# featherwing_RGBLEDmatrixPanel.net
KiCad netlist of a schematic drawn in EAGLE
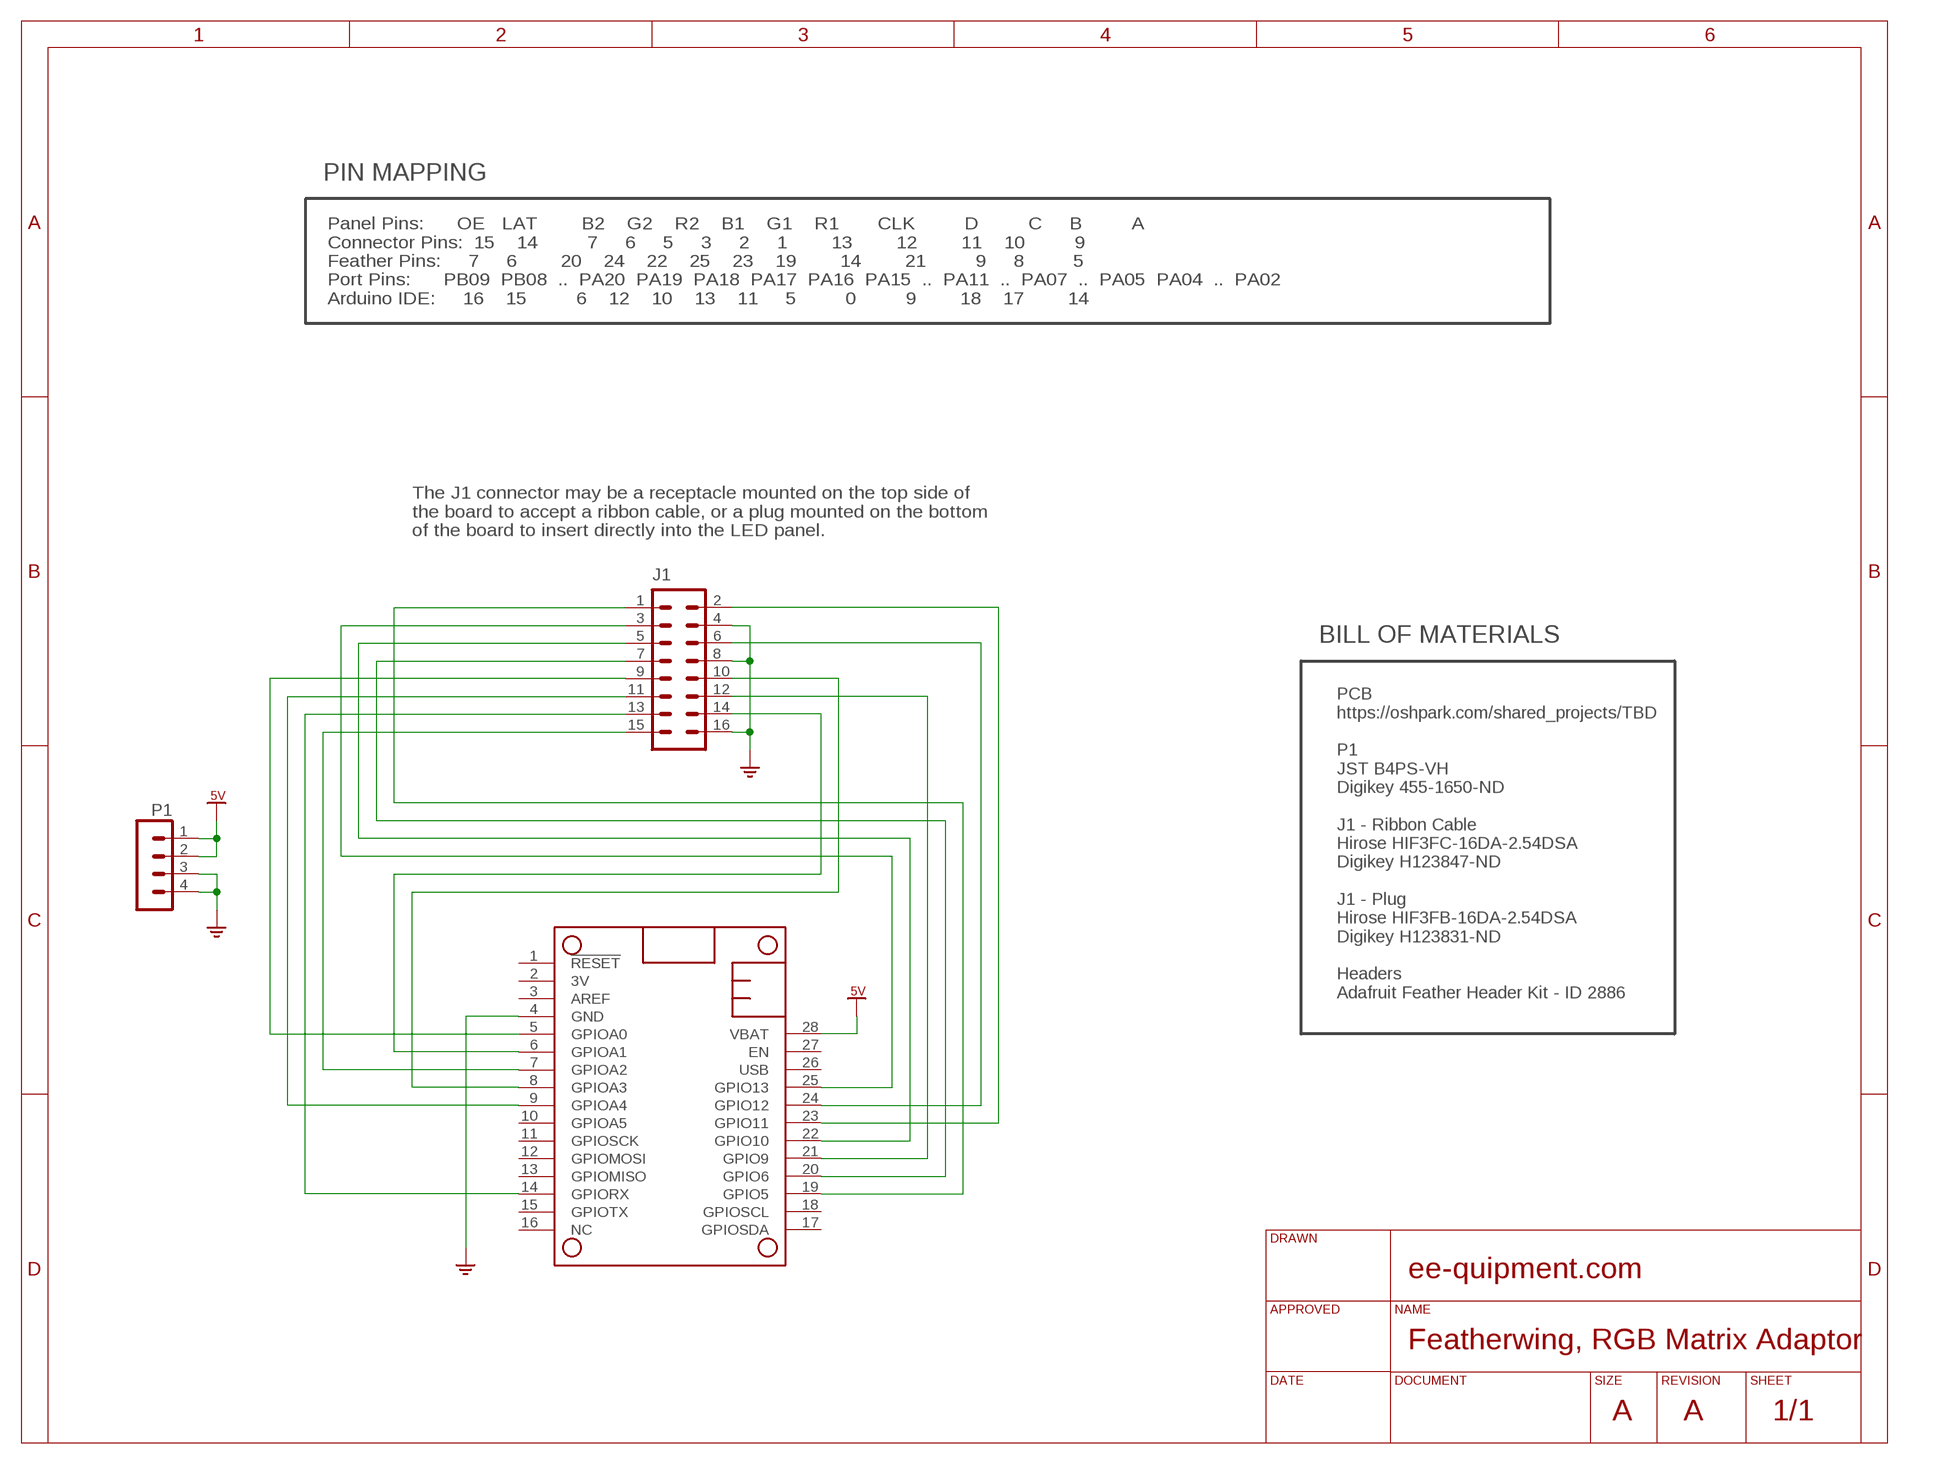
[diagram p0: schematic, sheet 1]

(export (version "E")
  (design (tool "Eeschema 10.0.6"))
  (components
    (comp (ref "J1")
      (value "HDR_16")
      (footprint "eagle-import:HDR_16")
      (libsource (lib "eagle-import") (part "HDR_16"))
    )
    (comp (ref "MS1")
      (value "MICROSHIELD")
      (footprint "eagle-import:MICROSHIELD")
      (libsource (lib "eagle-import") (part "MICROSHIELD"))
    )
    (comp (ref "P1")
      (value "JST_B4P-VHRA")
      (footprint "eagle-import:JST_B4PS-VH")
      (libsource (lib "eagle-import") (part "JST_B4P-VHRA"))
    )
  )
  (nets
    (net (code "1") (name "/3V") (class "Default")
      (node (ref "MS1") (pin "2") (pinfunction "3V_2") (pintype "power_in"))
    )
    (net (code "2") (name "/USB") (class "Default")
      (node (ref "MS1") (pin "26") (pinfunction "USB_26") (pintype "power_in"))
    )
    (net (code "3") (name "5V") (class "Default")
      (node (ref "MS1") (pin "28") (pinfunction "VBAT_28") (pintype "power_in"))
      (node (ref "P1") (pin "1") (pinfunction "1_1") (pintype "passive"))
      (node (ref "P1") (pin "2") (pinfunction "2_2") (pintype "passive"))
    )
    (net (code "4") (name "GND") (class "Default")
      (node (ref "J1") (pin "16") (pinfunction "16_16") (pintype "passive"))
      (node (ref "J1") (pin "4") (pinfunction "4_4") (pintype "passive"))
      (node (ref "J1") (pin "8") (pinfunction "8_8") (pintype "passive"))
      (node (ref "MS1") (pin "4") (pinfunction "GND_4") (pintype "power_in"))
      (node (ref "P1") (pin "3") (pinfunction "3_3") (pintype "passive"))
      (node (ref "P1") (pin "4") (pinfunction "4_4") (pintype "passive"))
    )
    (net (code "5") (name "Net-(MS1-GPIO5)") (class "Default")
      (node (ref "J1") (pin "1") (pinfunction "1_1") (pintype "passive"))
      (node (ref "MS1") (pin "19") (pinfunction "GPIO5_19") (pintype "bidirectional"))
    )
    (net (code "6") (name "Net-(MS1-GPIO6)") (class "Default")
      (node (ref "J1") (pin "7") (pinfunction "7_7") (pintype "passive"))
      (node (ref "MS1") (pin "20") (pinfunction "GPIO6_20") (pintype "bidirectional"))
    )
    (net (code "7") (name "Net-(MS1-GPIO9)") (class "Default")
      (node (ref "J1") (pin "12") (pinfunction "12_12") (pintype "passive"))
      (node (ref "MS1") (pin "21") (pinfunction "GPIO9_21") (pintype "bidirectional"))
    )
    (net (code "8") (name "Net-(MS1-GPIO10)") (class "Default")
      (node (ref "J1") (pin "5") (pinfunction "5_5") (pintype "passive"))
      (node (ref "MS1") (pin "22") (pinfunction "GPIO10_22") (pintype "bidirectional"))
    )
    (net (code "9") (name "Net-(MS1-GPIO11)") (class "Default")
      (node (ref "J1") (pin "2") (pinfunction "2_2") (pintype "passive"))
      (node (ref "MS1") (pin "23") (pinfunction "GPIO11_23") (pintype "bidirectional"))
    )
    (net (code "10") (name "Net-(MS1-GPIO12)") (class "Default")
      (node (ref "J1") (pin "6") (pinfunction "6_6") (pintype "passive"))
      (node (ref "MS1") (pin "24") (pinfunction "GPIO12_24") (pintype "bidirectional"))
    )
    (net (code "11") (name "Net-(MS1-GPIO13)") (class "Default")
      (node (ref "J1") (pin "3") (pinfunction "3_3") (pintype "passive"))
      (node (ref "MS1") (pin "25") (pinfunction "GPIO13_25") (pintype "bidirectional"))
    )
    (net (code "12") (name "Net-(MS1-GPIOA0)") (class "Default")
      (node (ref "J1") (pin "9") (pinfunction "9_9") (pintype "passive"))
      (node (ref "MS1") (pin "5") (pinfunction "GPIOA0_5") (pintype "bidirectional"))
    )
    (net (code "13") (name "Net-(MS1-GPIOA1)") (class "Default")
      (node (ref "J1") (pin "14") (pinfunction "14_14") (pintype "passive"))
      (node (ref "MS1") (pin "6") (pinfunction "GPIOA1_6") (pintype "bidirectional"))
    )
    (net (code "14") (name "Net-(MS1-GPIOA2)") (class "Default")
      (node (ref "J1") (pin "15") (pinfunction "15_15") (pintype "passive"))
      (node (ref "MS1") (pin "7") (pinfunction "GPIOA2_7") (pintype "bidirectional"))
    )
    (net (code "15") (name "Net-(MS1-GPIOA3)") (class "Default")
      (node (ref "J1") (pin "10") (pinfunction "10_10") (pintype "passive"))
      (node (ref "MS1") (pin "8") (pinfunction "GPIOA3_8") (pintype "bidirectional"))
    )
    (net (code "16") (name "Net-(MS1-GPIOA4)") (class "Default")
      (node (ref "J1") (pin "11") (pinfunction "11_11") (pintype "passive"))
      (node (ref "MS1") (pin "9") (pinfunction "GPIOA4_9") (pintype "bidirectional"))
    )
    (net (code "17") (name "Net-(MS1-GPIORX)") (class "Default")
      (node (ref "J1") (pin "13") (pinfunction "13_13") (pintype "passive"))
      (node (ref "MS1") (pin "14") (pinfunction "GPIORX_14") (pintype "bidirectional"))
    )
    (net (code "18") (name "unconnected-(MS1-AREF-Pad3)") (class "Default")
      (node (ref "MS1") (pin "3") (pinfunction "AREF_3") (pintype "passive"))
    )
    (net (code "19") (name "unconnected-(MS1-EN-Pad27)") (class "Default")
      (node (ref "MS1") (pin "27") (pinfunction "EN_27") (pintype "passive"))
    )
    (net (code "20") (name "unconnected-(MS1-GPIOA5-Pad10)") (class "Default")
      (node (ref "MS1") (pin "10") (pinfunction "GPIOA5_10") (pintype "bidirectional"))
    )
    (net (code "21") (name "unconnected-(MS1-GPIOMISO-Pad13)") (class "Default")
      (node (ref "MS1") (pin "13") (pinfunction "GPIOMISO_13") (pintype "bidirectional"))
    )
    (net (code "22") (name "unconnected-(MS1-GPIOMOSI-Pad12)") (class "Default")
      (node (ref "MS1") (pin "12") (pinfunction "GPIOMOSI_12") (pintype "bidirectional"))
    )
    (net (code "23") (name "unconnected-(MS1-GPIOSCK-Pad11)") (class "Default")
      (node (ref "MS1") (pin "11") (pinfunction "GPIOSCK_11") (pintype "bidirectional"))
    )
    (net (code "24") (name "unconnected-(MS1-GPIOSCL-Pad18)") (class "Default")
      (node (ref "MS1") (pin "18") (pinfunction "GPIOSCL_18") (pintype "bidirectional"))
    )
    (net (code "25") (name "unconnected-(MS1-GPIOSDA-Pad17)") (class "Default")
      (node (ref "MS1") (pin "17") (pinfunction "GPIOSDA_17") (pintype "bidirectional"))
    )
    (net (code "26") (name "unconnected-(MS1-GPIOTX-Pad15)") (class "Default")
      (node (ref "MS1") (pin "15") (pinfunction "GPIOTX_15") (pintype "bidirectional"))
    )
    (net (code "27") (name "unconnected-(MS1-NC-Pad16)") (class "Default")
      (node (ref "MS1") (pin "16") (pinfunction "NC_16") (pintype "passive"))
    )
    (net (code "28") (name "unconnected-(MS1-~{RESET}-Pad1)") (class "Default")
      (node (ref "MS1") (pin "1") (pinfunction "~{RESET}_1") (pintype "input"))
    )
  )
)
